# Output.net
KiCad netlist of a schematic drawn in Altium Designer
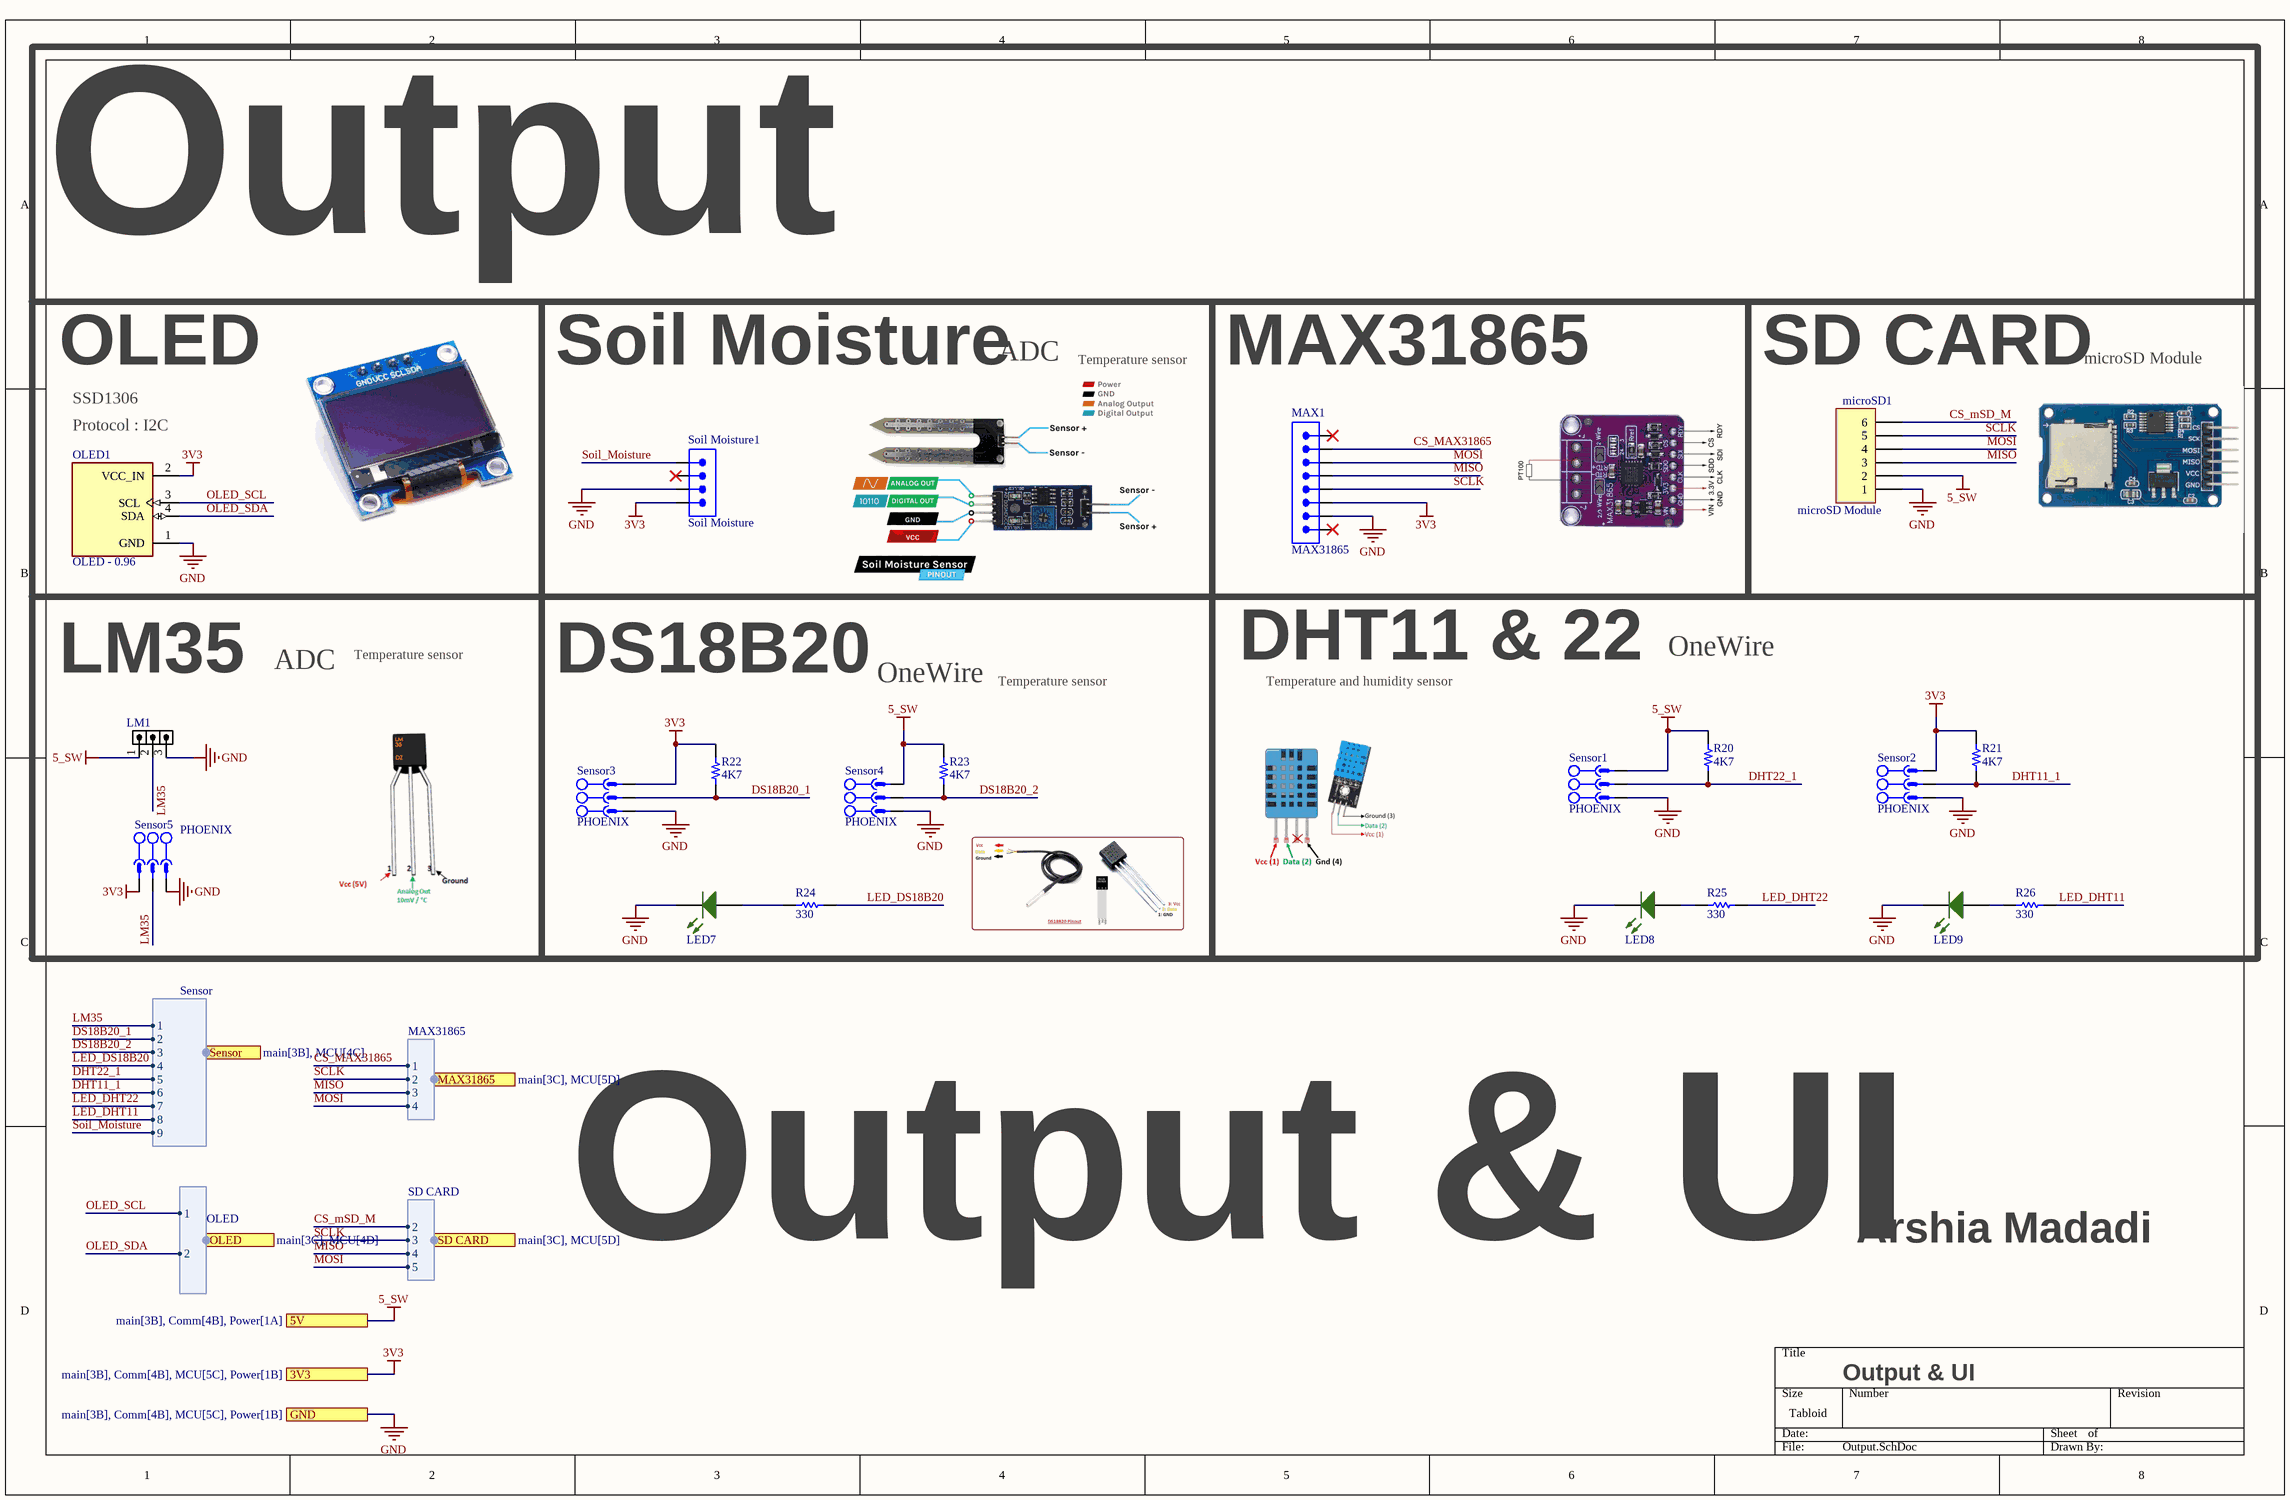
[diagram p0: Output.SchDoc]

(export (version "E")
  (design (tool "Eeschema 10.0.6"))
  (components
    (comp (ref "LED7")
      (value "LED SMD 0805 GREEN")
      (footprint "LED_0805_GREEN")
      (libsource (lib "Led") (part "LED SMD 0805 GREEN"))
    )
    (comp (ref "LED8")
      (value "LED SMD 0805 GREEN")
      (footprint "LED_0805_GREEN")
      (libsource (lib "") (part "LED SMD 0805 GREEN_1"))
    )
    (comp (ref "LED9")
      (value "LED SMD 0805 GREEN")
      (footprint "LED_0805_GREEN")
      (libsource (lib "Led") (part "LED SMD 0805 GREEN"))
    )
    (comp (ref "LM1")
      (value "HDRM3")
      (footprint "HDR_1X3")
      (description "CONN, HEADER, Male, pitch: 2.54mm, 3POS")
      (libsource (lib "Conn Header") (part "HDR_1X3"))
    )
    (comp (ref "MAX1")
      (value "MAX31865")
      (footprint "MHDR1X08-254P")
      (description "Male Header 1X08")
      (libsource (lib "SJ Sockets & Connectors") (part "MHDR_1X08"))
    )
    (comp (ref "microSD1")
      (value "microSD Module")
      (footprint "HDR1X6-1")
      (description "Header, 6-Pin")
      (fields (field (name "PUBLISHER") "Altium Limited"))
      (libsource (lib "Altium") (part "Header 6"))
    )
    (comp (ref "OLED1")
      (value "OLED - 0.96")
      (footprint "MODULE_DM-OLED096-636")
      (description "0.96â€ 128 X 64 MONOCHROME GRAPHIC OLED DISPLAY MODULE - I2C")
      (fields (field (name "MF") "Display Module") (field (name "MP") "DM-OLED096-636"))
      (libsource (lib "DM-OLED096-636") (part "DM-OLED096-636"))
    )
    (comp (ref "R20")
      (value "4K7")
      (footprint "RES 0603_1608")
      (description "RES 0603")
      (libsource (lib "Resistor") (part "Res 0603"))
    )
    (comp (ref "R21")
      (value "4K7")
      (footprint "RES 0603_1608")
      (description "RES 0603")
      (libsource (lib "Resistor") (part "Res 0603"))
    )
    (comp (ref "R22")
      (value "4K7")
      (footprint "RES 0603_1608")
      (description "RES 0603")
      (libsource (lib "Resistor") (part "Res 0603"))
    )
    (comp (ref "R23")
      (value "4K7")
      (footprint "RES 0603_1608")
      (description "RES 0603")
      (libsource (lib "Resistor") (part "Res 0603"))
    )
    (comp (ref "R24")
      (value "330")
      (footprint "RESC3413X04N")
      (description "RES 0805")
      (fields (field (name "DESIGNER") "Abbas Basereh"))
      (libsource (lib "Altium") (part "RES 0805 0.125W"))
    )
    (comp (ref "R25")
      (value "330")
      (footprint "RESC3413X04N")
      (description "RES 0805")
      (fields (field (name "DESIGNER") "Abbas Basereh"))
      (libsource (lib "Altium") (part "RES 0805 0.125W"))
    )
    (comp (ref "R26")
      (value "330")
      (footprint "RESC3413X04N")
      (description "RES 0805")
      (fields (field (name "DESIGNER") "Abbas Basereh"))
      (libsource (lib "Altium") (part "RES 0805 0.125W"))
    )
    (comp (ref "Sensor1")
      (value "PHOENIX")
      (footprint "MSTB 2,5/3-G-5,08")
      (description "3 Pitch: 5.08 mm Color: green Contact surface: Tin Assembly")
      (fields
        (field (name "MANUFACTURER") "PHOENIX CONTACT")
        (field (name "VOLTAGE") "320 V")
        (field (name "DESIGNER") "ABBAS BASEREH")
      )
      (libsource (lib "Altium") (part "CON_Phoenix_MSTB_03"))
    )
    (comp (ref "Sensor2")
      (value "PHOENIX")
      (footprint "MSTB 2,5/3-G-5,08")
      (description "3 Pitch: 5.08 mm Color: green Contact surface: Tin Assembly")
      (fields
        (field (name "MANUFACTURER") "PHOENIX CONTACT")
        (field (name "VOLTAGE") "320 V")
        (field (name "DESIGNER") "ABBAS BASEREH")
      )
      (libsource (lib "Altium") (part "CON_Phoenix_MSTB_03"))
    )
    (comp (ref "Sensor3")
      (value "PHOENIX")
      (footprint "MSTB 2,5/3-G-5,08")
      (description "3 Pitch: 5.08 mm Color: green Contact surface: Tin Assembly")
      (fields
        (field (name "MANUFACTURER") "PHOENIX CONTACT")
        (field (name "VOLTAGE") "320 V")
        (field (name "DESIGNER") "ABBAS BASEREH")
      )
      (libsource (lib "Altium") (part "CON_Phoenix_MSTB_03"))
    )
    (comp (ref "Sensor4")
      (value "PHOENIX")
      (footprint "MSTB 2,5/3-G-5,08")
      (description "3 Pitch: 5.08 mm Color: green Contact surface: Tin Assembly")
      (fields
        (field (name "MANUFACTURER") "PHOENIX CONTACT")
        (field (name "VOLTAGE") "320 V")
        (field (name "DESIGNER") "ABBAS BASEREH")
      )
      (libsource (lib "Altium") (part "CON_Phoenix_MSTB_03"))
    )
    (comp (ref "Sensor5")
      (value "PHOENIX")
      (footprint "MSTB 2,5/3-G-5,08")
      (description "3 Pitch: 5.08 mm Color: green Contact surface: Tin Assembly")
      (fields
        (field (name "MANUFACTURER") "PHOENIX CONTACT")
        (field (name "VOLTAGE") "320 V")
        (field (name "DESIGNER") "ABBAS BASEREH")
      )
      (libsource (lib "Altium") (part "CON_Phoenix_MSTB_03"))
    )
    (comp (ref "Soil Moisture1")
      (value "Soil Moisture")
      (footprint "MHDR1X04-254P")
      (description "Male Header 1X04")
      (libsource (lib "SJ Sockets & Connectors") (part "MHDR_1X04"))
    )
  )
  (nets
    (net (code "6") (name "/CS_MAX31865") (class "Default")
      (node (ref "MAX1") (pin "2") (pinfunction "2_2") (pintype "passive"))
    )
    (net (code "7") (name "/CS_mSD_M") (class "Default")
      (node (ref "microSD1") (pin "6") (pinfunction "6_6") (pintype "passive"))
    )
    (net (code "8") (name "/DHT11_1") (class "Default")
      (node (ref "R21") (pin "1") (pinfunction "1_1") (pintype "passive"))
      (node (ref "Sensor2") (pin "2") (pinfunction "2_2") (pintype "passive"))
    )
    (net (code "9") (name "/DHT22_1") (class "Default")
      (node (ref "R20") (pin "1") (pinfunction "1_1") (pintype "passive"))
      (node (ref "Sensor1") (pin "2") (pinfunction "2_2") (pintype "passive"))
    )
    (net (code "10") (name "/DS18B20_1") (class "Default")
      (node (ref "R22") (pin "1") (pinfunction "1_1") (pintype "passive"))
      (node (ref "Sensor3") (pin "2") (pinfunction "2_2") (pintype "passive"))
    )
    (net (code "11") (name "/DS18B20_2") (class "Default")
      (node (ref "R23") (pin "1") (pinfunction "1_1") (pintype "passive"))
      (node (ref "Sensor4") (pin "2") (pinfunction "2_2") (pintype "passive"))
    )
    (net (code "12") (name "/LED_DHT11") (class "Default")
      (node (ref "R26") (pin "1") (pinfunction "1_1") (pintype "passive"))
    )
    (net (code "13") (name "/LED_DHT22") (class "Default")
      (node (ref "R25") (pin "1") (pinfunction "1_1") (pintype "passive"))
    )
    (net (code "14") (name "/LED_DS18B20") (class "Default")
      (node (ref "R24") (pin "1") (pinfunction "1_1") (pintype "passive"))
    )
    (net (code "15") (name "/LM35") (class "Default")
      (node (ref "LM1") (pin "2") (pinfunction "2_2") (pintype "passive"))
      (node (ref "Sensor5") (pin "2") (pinfunction "2_2") (pintype "passive"))
    )
    (net (code "16") (name "/MISO") (class "Default")
      (node (ref "MAX1") (pin "4") (pinfunction "4_4") (pintype "passive"))
      (node (ref "microSD1") (pin "3") (pinfunction "3_3") (pintype "passive"))
    )
    (net (code "17") (name "/MOSI") (class "Default")
      (node (ref "MAX1") (pin "3") (pinfunction "3_3") (pintype "passive"))
      (node (ref "microSD1") (pin "4") (pinfunction "4_4") (pintype "passive"))
    )
    (net (code "18") (name "/OLED_SCL") (class "Default")
      (node (ref "OLED1") (pin "3") (pinfunction "SCL_3") (pintype "input"))
    )
    (net (code "19") (name "/OLED_SDA") (class "Default")
      (node (ref "OLED1") (pin "4") (pinfunction "SDA_4") (pintype "bidirectional"))
    )
    (net (code "20") (name "/SCLK") (class "Default")
      (node (ref "MAX1") (pin "5") (pinfunction "5_5") (pintype "passive"))
      (node (ref "microSD1") (pin "5") (pinfunction "5_5") (pintype "passive"))
    )
    (net (code "21") (name "/Soil_Moisture") (class "Default")
      (node (ref "Soil Moisture1") (pin "1") (pinfunction "1_1") (pintype "passive"))
    )
    (net (code "26") (name "3V3") (class "Default")
      (node (ref "MAX1") (pin "6") (pinfunction "6_6") (pintype "passive"))
      (node (ref "OLED1") (pin "2") (pinfunction "VCC_IN_2") (pintype "power_in"))
      (node (ref "R21") (pin "2") (pinfunction "2_2") (pintype "passive"))
      (node (ref "R22") (pin "2") (pinfunction "2_2") (pintype "passive"))
      (node (ref "Sensor2") (pin "1") (pinfunction "1_1") (pintype "passive"))
      (node (ref "Sensor3") (pin "1") (pinfunction "1_1") (pintype "passive"))
      (node (ref "Sensor5") (pin "3") (pinfunction "3_3") (pintype "passive"))
      (node (ref "Soil Moisture1") (pin "4") (pinfunction "4_4") (pintype "passive"))
    )
    (net (code "27") (name "5_SW") (class "Default")
      (node (ref "LM1") (pin "1") (pinfunction "1_1") (pintype "passive"))
      (node (ref "R20") (pin "2") (pinfunction "2_2") (pintype "passive"))
      (node (ref "R23") (pin "2") (pinfunction "2_2") (pintype "passive"))
      (node (ref "Sensor1") (pin "1") (pinfunction "1_1") (pintype "passive"))
      (node (ref "Sensor4") (pin "1") (pinfunction "1_1") (pintype "passive"))
      (node (ref "microSD1") (pin "2") (pinfunction "2_2") (pintype "passive"))
    )
    (net (code "28") (name "GND") (class "Default")
      (node (ref "LED7") (pin "2") (pinfunction "K_2") (pintype "passive"))
      (node (ref "LED8") (pin "1") (pinfunction "A_1") (pintype "passive"))
      (node (ref "LED9") (pin "2") (pinfunction "K_2") (pintype "passive"))
      (node (ref "LM1") (pin "3") (pinfunction "3_3") (pintype "passive"))
      (node (ref "MAX1") (pin "7") (pinfunction "7_7") (pintype "passive"))
      (node (ref "OLED1") (pin "1") (pinfunction "GND_1") (pintype "power_in"))
      (node (ref "Sensor1") (pin "3") (pinfunction "3_3") (pintype "passive"))
      (node (ref "Sensor2") (pin "3") (pinfunction "3_3") (pintype "passive"))
      (node (ref "Sensor3") (pin "3") (pinfunction "3_3") (pintype "passive"))
      (node (ref "Sensor4") (pin "3") (pinfunction "3_3") (pintype "passive"))
      (node (ref "Sensor5") (pin "1") (pinfunction "1_1") (pintype "passive"))
      (node (ref "Soil Moisture1") (pin "3") (pinfunction "3_3") (pintype "passive"))
      (node (ref "microSD1") (pin "1") (pinfunction "1_1") (pintype "passive"))
    )
    (net (code "29") (name "Net-(LED7-A)") (class "Default")
      (node (ref "LED7") (pin "1") (pinfunction "A_1") (pintype "passive"))
      (node (ref "R24") (pin "2") (pinfunction "2_2") (pintype "passive"))
    )
    (net (code "30") (name "Net-(LED8-K)") (class "Default")
      (node (ref "LED8") (pin "2") (pinfunction "K_2") (pintype "passive"))
      (node (ref "R25") (pin "2") (pinfunction "2_2") (pintype "passive"))
    )
    (net (code "31") (name "Net-(LED9-A)") (class "Default")
      (node (ref "LED9") (pin "1") (pinfunction "A_1") (pintype "passive"))
      (node (ref "R26") (pin "2") (pinfunction "2_2") (pintype "passive"))
    )
    (net (code "32") (name "unconnected-(MAX1-Pad1)") (class "Default")
      (node (ref "MAX1") (pin "1") (pinfunction "1_1") (pintype "passive+no_connect"))
    )
    (net (code "33") (name "unconnected-(MAX1-Pad8)") (class "Default")
      (node (ref "MAX1") (pin "8") (pinfunction "8_8") (pintype "passive+no_connect"))
    )
    (net (code "34") (name "unconnected-(Soil Moisture1-Pad2)") (class "Default")
      (node (ref "Soil Moisture1") (pin "2") (pinfunction "2_2") (pintype "passive+no_connect"))
    )
  )
)
